# TOPCPCB_IXYS.net
KiCad netlist of a schematic drawn in EAGLE
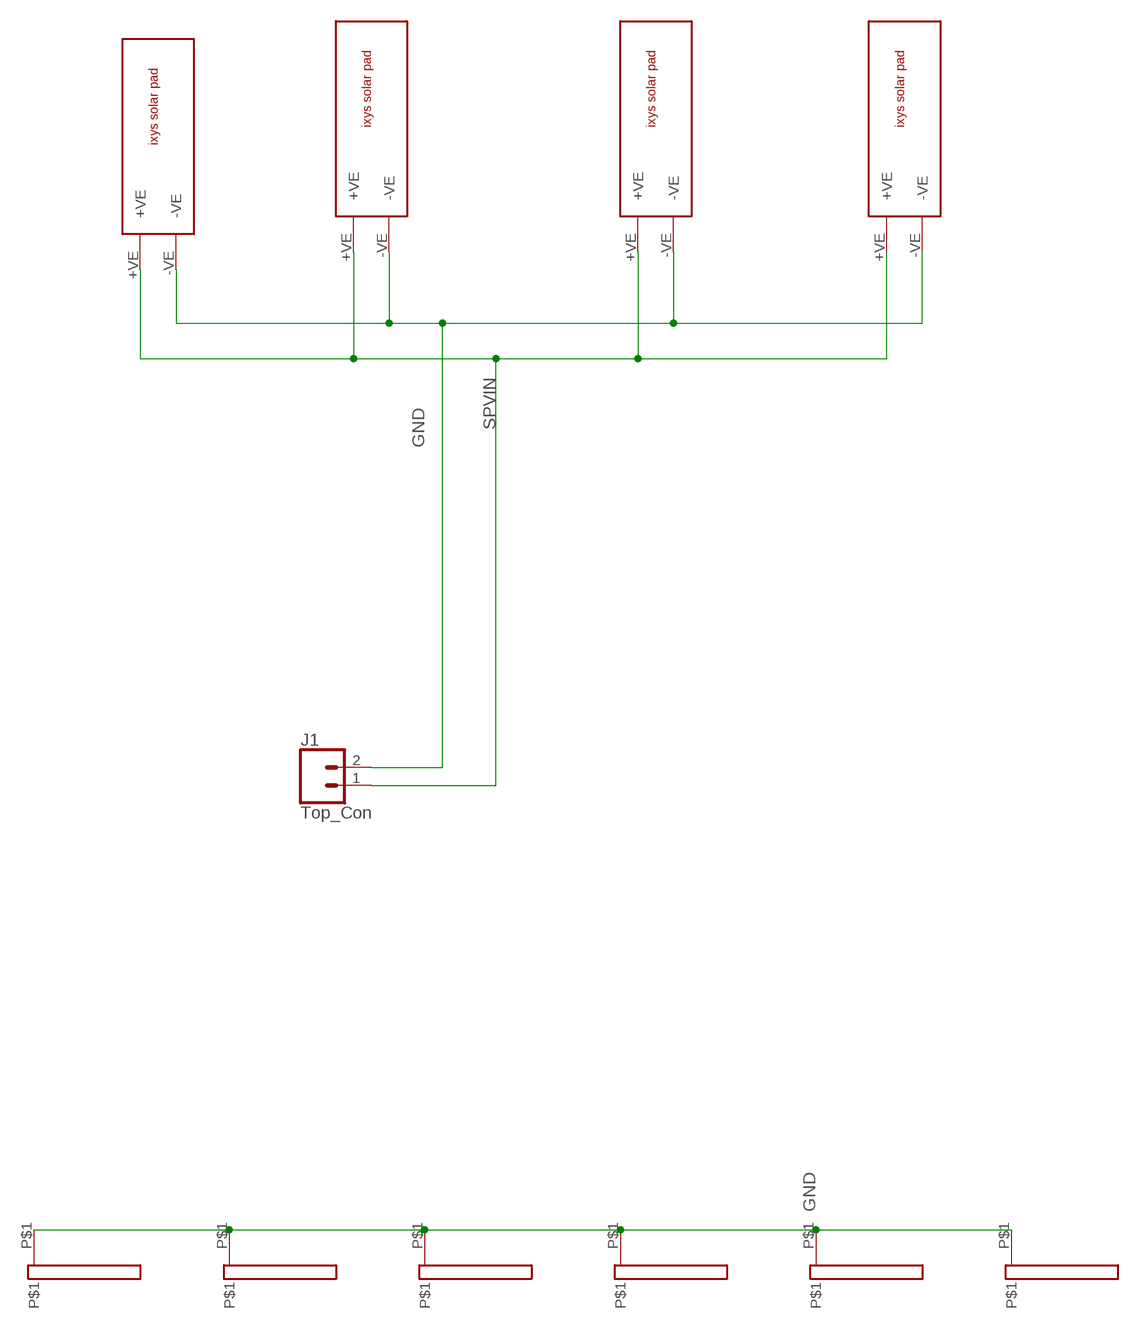
[diagram p0: schematic, sheet 1]

(export (version "E")
  (design (tool "Eeschema 10.0.6"))
  (components
    (comp (ref "J1")
      (value "Top_Con")
      (footprint "eagle-import:1X02")
      (libsource (lib "eagle-import") (part "CONN_02"))
    )
    (comp (ref "LEFTSOLD")
      (value "16X2")
      (footprint "eagle-import:16X2")
      (libsource (lib "eagle-import") (part "16X2"))
    )
    (comp (ref "U$1")
      (value "16X2")
      (footprint "eagle-import:16X2")
      (libsource (lib "eagle-import") (part "16X2"))
    )
    (comp (ref "U$2")
      (value "IXYS")
      (footprint "eagle-import:IXYS")
      (libsource (lib "eagle-import") (part "IXYS"))
    )
    (comp (ref "U$3")
      (value "IXYS")
      (footprint "eagle-import:IXYS")
      (libsource (lib "eagle-import") (part "IXYS"))
    )
    (comp (ref "U$4")
      (value "16X2")
      (footprint "eagle-import:16X2")
      (libsource (lib "eagle-import") (part "16X2"))
    )
    (comp (ref "U$5")
      (value "16X2")
      (footprint "eagle-import:16X2")
      (libsource (lib "eagle-import") (part "16X2"))
    )
    (comp (ref "U$6")
      (value "IXYS")
      (footprint "eagle-import:IXYS")
      (libsource (lib "eagle-import") (part "IXYS"))
    )
    (comp (ref "U$7")
      (value "16X2")
      (footprint "eagle-import:16X2")
      (libsource (lib "eagle-import") (part "16X2"))
    )
    (comp (ref "U$8")
      (value "IXYS")
      (footprint "eagle-import:IXYS")
      (libsource (lib "eagle-import") (part "IXYS"))
    )
    (comp (ref "U$9")
      (value "16X2")
      (footprint "eagle-import:16X2")
      (libsource (lib "eagle-import") (part "16X2"))
    )
  )
  (nets
    (net (code "1") (name "/GND") (class "Default")
      (node (ref "J1") (pin "2") (pinfunction "2_2") (pintype "passive"))
      (node (ref "LEFTSOLD") (pin "P$1") (pinfunction "P$1_P$1") (pintype "bidirectional"))
      (node (ref "U$1") (pin "P$1") (pinfunction "P$1_P$1") (pintype "bidirectional"))
      (node (ref "U$2") (pin "-VE") (pinfunction "-VE_-VE") (pintype "bidirectional"))
      (node (ref "U$3") (pin "-VE") (pinfunction "-VE_-VE") (pintype "bidirectional"))
      (node (ref "U$4") (pin "P$1") (pinfunction "P$1_P$1") (pintype "bidirectional"))
      (node (ref "U$5") (pin "P$1") (pinfunction "P$1_P$1") (pintype "bidirectional"))
      (node (ref "U$6") (pin "-VE") (pinfunction "-VE_-VE") (pintype "bidirectional"))
      (node (ref "U$7") (pin "P$1") (pinfunction "P$1_P$1") (pintype "bidirectional"))
      (node (ref "U$8") (pin "-VE") (pinfunction "-VE_-VE") (pintype "bidirectional"))
      (node (ref "U$9") (pin "P$1") (pinfunction "P$1_P$1") (pintype "bidirectional"))
    )
    (net (code "2") (name "/SPVIN") (class "Default")
      (node (ref "J1") (pin "1") (pinfunction "1_1") (pintype "passive"))
      (node (ref "U$2") (pin "+VE") (pinfunction "+VE_+VE") (pintype "bidirectional"))
      (node (ref "U$3") (pin "+VE") (pinfunction "+VE_+VE") (pintype "bidirectional"))
      (node (ref "U$6") (pin "+VE") (pinfunction "+VE_+VE") (pintype "bidirectional"))
      (node (ref "U$8") (pin "+VE") (pinfunction "+VE_+VE") (pintype "bidirectional"))
    )
  )
)
